# Receiver.net
KiCad netlist of a schematic drawn in Altium Designer
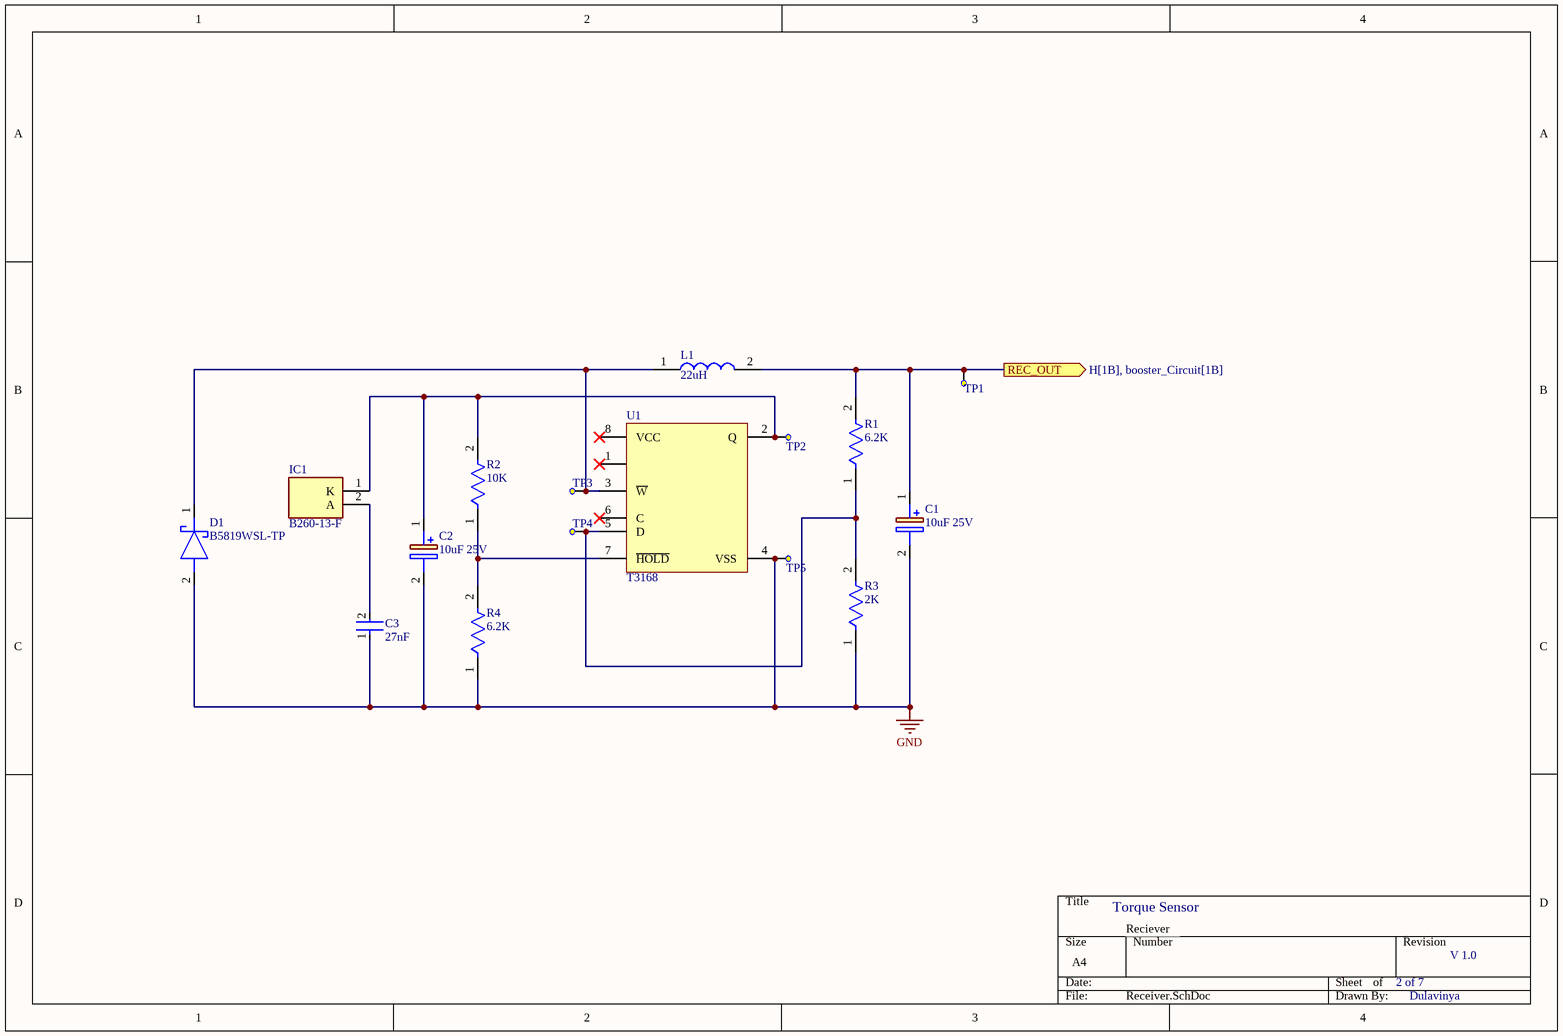
[diagram p0: Receiver.SchDoc]

(export (version "E")
  (design (tool "Eeschema 10.0.6"))
  (components
    (comp (ref "C1")
      (value "10uF 25V")
      (footprint "SamacSys:CAPAE660X565N")
      (description "Capacitor Polarised")
      (fields
        (field (name "MANUFACTURER_PART_NUMBER") "EDK106M025A9BAA")
        (field (name "MOUSER PART NUMBER") "80-EDK106M025A9BAA")
      )
      (libsource (lib "*") (part "EDK106M025A9BAA"))
    )
    (comp (ref "C2")
      (value "10uF 25V")
      (footprint "SamacSys:CAPAE660X565N")
      (description "Capacitor Polarised")
      (fields
        (field (name "MANUFACTURER_PART_NUMBER") "EDK106M025A9BAA")
        (field (name "MOUSER PART NUMBER") "80-EDK106M025A9BAA")
      )
      (libsource (lib "*") (part "EDK106M025A9BAA"))
    )
    (comp (ref "C3")
      (value "27nF")
      (footprint "FP-CL05A106MP5NUNC-MFG")
      (description "CAP CER 10UF 10V X5R 0402")
      (fields
        (field (name "OCTOPART") "https://octopart.com/cl05a106mp5nunc-samsung-22457395")
        (field (name "TOLERANCE") "20%")
      )
      (libsource (lib "Altium Content Vault") (part "b4654b650e69147ec39a6b967a45e02"))
    )
    (comp (ref "D1")
      (value "B5819WSL-TP")
      (footprint "SamacSys:SODFL2512X90N")
      (description "Schottky Diode")
      (fields (field (name "MOUSER PART NUMBER") "833-B5819WSL-TP"))
      (libsource (lib "*") (part "B5819WSL-TP"))
    )
    (comp (ref "IC1")
      (value "B260-13-F")
      (footprint "SamacSys:DIOM5336X250N")
      (description "Integrated Circuit")
      (fields (field (name "MOUSER PART NUMBER") "621-B260-F"))
      (libsource (lib "*") (part "B260-13-F"))
    )
    (comp (ref "L1")
      (value "22uH")
      (footprint "SamacSys:INDPM6868X420N")
      (description "Inductor")
      (fields
        (field (name "MANUFACTURER_PART_NUMBER") "SRR6838A-220M")
        (field (name "MOUSER PART NUMBER") "652-SRR6838A-220M")
      )
      (libsource (lib "*") (part "SRR6838A-220M"))
    )
    (comp (ref "R1")
      (value "6.2K")
      (footprint "FP-ERJ2R-MFG")
      (description "RES SMD 15K OHM 1% 1/10W 0402")
      (fields (field (name "TOLERANCE") "1%") (field (name "MANUFACTURER PART NUMBER") "ERJ-2RKF1502X"))
      (libsource (lib "Altium Content Vault") (part "1029c3af85768c4190bb7ad29bc67b5"))
    )
    (comp (ref "R2")
      (value "10K")
      (footprint "FP-ERJ2R-MFG")
      (description "RES SMD 15K OHM 1% 1/10W 0402")
      (fields (field (name "TOLERANCE") "1%") (field (name "MANUFACTURER PART NUMBER") "ERJ-2RKF1502X"))
      (libsource (lib "Altium Content Vault") (part "1029c3af85768c4190bb7ad29bc67b5"))
    )
    (comp (ref "R3")
      (value "2K")
      (footprint "FP-ERJ2R-MFG")
      (description "RES SMD 15K OHM 1% 1/10W 0402")
      (fields (field (name "TOLERANCE") "1%") (field (name "MANUFACTURER PART NUMBER") "ERJ-2RKF1502X"))
      (libsource (lib "Altium Content Vault") (part "1029c3af85768c4190bb7ad29bc67b5"))
    )
    (comp (ref "R4")
      (value "6.2K")
      (footprint "FP-ERJ2R-MFG")
      (description "RES SMD 15K OHM 1% 1/10W 0402")
      (fields (field (name "TOLERANCE") "1%") (field (name "MANUFACTURER PART NUMBER") "ERJ-2RKF1502X"))
      (libsource (lib "Altium Content Vault") (part "1029c3af85768c4190bb7ad29bc67b5"))
    )
    (comp (ref "TP1")
      (value "Test point")
      (footprint "Test_point")
      (libsource (lib "Schlib1") (part "test_point"))
    )
    (comp (ref "TP2")
      (value "Test point")
      (footprint "Test_point")
      (libsource (lib "Schlib1") (part "test_point"))
    )
    (comp (ref "TP3")
      (value "Test point")
      (footprint "Test_point")
      (libsource (lib "Schlib1") (part "test_point"))
    )
    (comp (ref "TP4")
      (value "Test point")
      (footprint "Test_point")
      (libsource (lib "Schlib1") (part "test_point"))
    )
    (comp (ref "TP5")
      (value "Test point")
      (footprint "Test_point")
      (libsource (lib "Schlib1") (part "test_point"))
    )
    (comp (ref "U1")
      (value "T3168")
      (footprint "SOP127P600X173-8_PRSP0008DF-B_N")
      (description "Serial Peripheral Interface 32k EEPROM (4-kword × 8-bit) 64k EEPROM (8-kword × 8-bit)")
      (libsource (lib "Altium Content Vault") (part "f4225b3ad442a44c874fac446cf76bb"))
    )
  )
  (nets
    (net (code "1") (name "/REC_OUT") (class "Default")
      (node (ref "C1") (pin "1") (pinfunction "+_1") (pintype "passive"))
      (node (ref "L1") (pin "2") (pinfunction "2_2") (pintype "passive"))
      (node (ref "R1") (pin "2") (pinfunction "2_2") (pintype "passive"))
      (node (ref "TP1") (pin "TP?") (pinfunction "Test_point_TP?") (pintype "passive"))
    )
    (net (code "2") (name "GND") (class "Default")
      (node (ref "C1") (pin "2") (pinfunction "-_2") (pintype "passive"))
      (node (ref "C2") (pin "2") (pinfunction "-_2") (pintype "passive"))
      (node (ref "C3") (pin "1") (pinfunction "1_1") (pintype "passive"))
      (node (ref "D1") (pin "2") (pinfunction "A_2") (pintype "passive"))
      (node (ref "R3") (pin "1") (pinfunction "1_1") (pintype "passive"))
      (node (ref "R4") (pin "1") (pinfunction "1_1") (pintype "passive"))
      (node (ref "TP5") (pin "TP?") (pinfunction "Test_point_TP?") (pintype "passive"))
      (node (ref "U1") (pin "4") (pinfunction "VSS_4") (pintype "power_in"))
    )
    (net (code "3") (name "Net-(C2-+)") (class "Default")
      (node (ref "C2") (pin "1") (pinfunction "+_1") (pintype "passive"))
      (node (ref "IC1") (pin "1") (pinfunction "K_1") (pintype "passive"))
      (node (ref "R2") (pin "2") (pinfunction "2_2") (pintype "passive"))
      (node (ref "TP2") (pin "TP?") (pinfunction "Test_point_TP?") (pintype "passive"))
      (node (ref "U1") (pin "2") (pinfunction "Q_2") (pintype "passive"))
    )
    (net (code "4") (name "Net-(D1-K)") (class "Default")
      (node (ref "D1") (pin "1") (pinfunction "K_1") (pintype "passive"))
      (node (ref "L1") (pin "1") (pinfunction "1_1") (pintype "passive"))
      (node (ref "TP3") (pin "TP?") (pinfunction "Test_point_TP?") (pintype "passive"))
      (node (ref "U1") (pin "3") (pinfunction "~{W}_3") (pintype "passive"))
    )
    (net (code "5") (name "Net-(IC1-A)") (class "Default")
      (node (ref "C3") (pin "2") (pinfunction "2_2") (pintype "passive"))
      (node (ref "IC1") (pin "2") (pinfunction "A_2") (pintype "passive"))
    )
    (net (code "6") (name "Net-(TP4-Test_point)") (class "Default")
      (node (ref "R1") (pin "1") (pinfunction "1_1") (pintype "passive"))
      (node (ref "R3") (pin "2") (pinfunction "2_2") (pintype "passive"))
      (node (ref "TP4") (pin "TP?") (pinfunction "Test_point_TP?") (pintype "passive"))
      (node (ref "U1") (pin "5") (pinfunction "D_5") (pintype "passive"))
    )
    (net (code "7") (name "Net-(U1-~{HOLD})") (class "Default")
      (node (ref "R2") (pin "1") (pinfunction "1_1") (pintype "passive"))
      (node (ref "R4") (pin "2") (pinfunction "2_2") (pintype "passive"))
      (node (ref "U1") (pin "7") (pinfunction "~{HOLD}_7") (pintype "passive"))
    )
    (net (code "8") (name "unconnected-(U1-C-Pad6)") (class "Default")
      (node (ref "U1") (pin "6") (pinfunction "C_6") (pintype "passive+no_connect"))
    )
    (net (code "9") (name "unconnected-(U1-VCC-Pad8)") (class "Default")
      (node (ref "U1") (pin "8") (pinfunction "VCC_8") (pintype "power_in+no_connect"))
    )
    (net (code "10") (name "unconnected-(U1-~{S}-Pad1)") (class "Default")
      (node (ref "U1") (pin "1") (pinfunction "~{S}_1") (pintype "passive+no_connect"))
    )
  )
)
